# PWM_I2C.net
KiCad netlist of a schematic drawn in Altium Designer
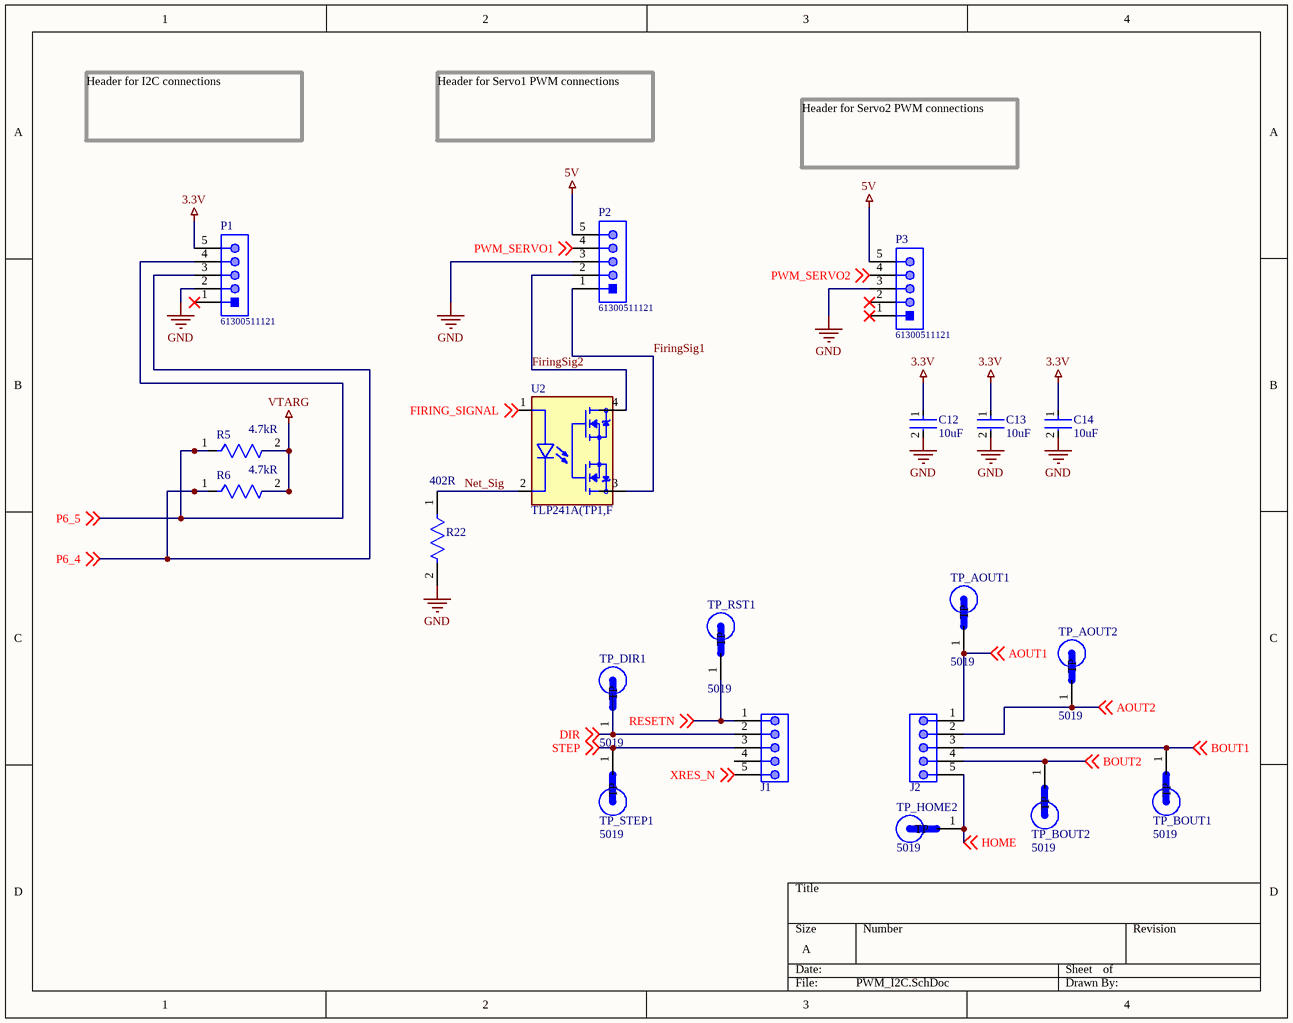
[diagram p0: PWM_I2C.SchDoc]

(export (version "E")
  (design (tool "Eeschema 10.0.6"))
  (components
    (comp (ref "C12")
      (value "10uF")
      (footprint "FP-C0805C-DG-MFG")
      (description "CAP CER 10UF 10V X5R 0805")
      (fields (field (name "TOLERANCE") "10%") (field (name "MANUFACTURER PART NUMBER") "C0805C106K8PACTU"))
      (libsource (lib "Altium Content Vault") (part "11868f565c42a9108669ba33697ecf6"))
    )
    (comp (ref "C13")
      (value "10uF")
      (footprint "FP-C0805C-DG-MFG")
      (description "CAP CER 10UF 10V X5R 0805")
      (fields (field (name "TOLERANCE") "10%") (field (name "MANUFACTURER PART NUMBER") "C0805C106K8PACTU"))
      (libsource (lib "Altium Content Vault") (part "11868f565c42a9108669ba33697ecf6"))
    )
    (comp (ref "C14")
      (value "10uF")
      (footprint "FP-C0805C-DG-MFG")
      (description "CAP CER 10UF 10V X5R 0805")
      (fields (field (name "TOLERANCE") "10%") (field (name "MANUFACTURER PART NUMBER") "C0805C106K8PACTU"))
      (libsource (lib "Altium Content Vault") (part "11868f565c42a9108669ba33697ecf6"))
    )
    (comp (ref "J1")
      (value "CONN_HEADER_MALE_1x5")
      (footprint "HDR1X5")
      (description "Header, 5-Pin")
      (libsource (lib "") (part "CONN_HEADER_MALE_1x5_1"))
    )
    (comp (ref "J2")
      (value "CONN_HEADER_MALE_1x5")
      (footprint "HDR1X5")
      (description "Header, 5-Pin")
      (libsource (lib "Connectors") (part "CONN_HEADER_MALE_1x5"))
    )
    (comp (ref "P1")
      (value "61300511121")
      (footprint "61300511121")
      (description "THT Vertical Pin Header WR-PHD, Pitch 2.54 mm, Single Row, 5 pins")
      (fields (field (name "MANUFACTURER") "Wurth Elektronik") (field (name "PUBLISHER") "WurthElektronik"))
      (libsource (lib "Altium Content Vault") (part "WE-CN-1P-M-R5"))
    )
    (comp (ref "P2")
      (value "61300511121")
      (footprint "61300511121")
      (description "THT Vertical Pin Header WR-PHD, Pitch 2.54 mm, Single Row, 5 pins")
      (fields (field (name "MANUFACTURER") "Wurth Elektronik") (field (name "PUBLISHER") "WurthElektronik"))
      (libsource (lib "Altium Content Vault") (part "WE-CN-1P-M-R5"))
    )
    (comp (ref "P3")
      (value "61300511121")
      (footprint "61300511121")
      (description "THT Vertical Pin Header WR-PHD, Pitch 2.54 mm, Single Row, 5 pins")
      (fields (field (name "MANUFACTURER") "Wurth Elektronik") (field (name "PUBLISHER") "WurthElektronik"))
      (libsource (lib "Altium Content Vault") (part "WE-CN-1P-M-R5"))
    )
    (comp (ref "R5")
      (value "RMCF0805JT4K70")
      (footprint "FP-RMCF0805-MFG")
      (description "4.7kΩ ±5% 0.125W 0805 Thick Film Chip Resistor AEC-Q200 compliant")
      (fields
        (field (name "RESISTANCE") "4.7kR")
        (field (name "TOLERANCE") "5%")
        (field (name "MANUFACTURER") "Stackpole Electronics")
      )
      (libsource (lib "Altium Content Vault") (part "1029c3af85768c4190bb7ad29bc67b5"))
    )
    (comp (ref "R6")
      (value "RMCF0805JT4K70")
      (footprint "FP-RMCF0805-MFG")
      (description "4.7kΩ ±5% 0.125W 0805 Thick Film Chip Resistor AEC-Q200 compliant")
      (fields
        (field (name "RESISTANCE") "4.7kR")
        (field (name "TOLERANCE") "5%")
        (field (name "MANUFACTURER") "Stackpole Electronics")
      )
      (libsource (lib "Altium Content Vault") (part "1029c3af85768c4190bb7ad29bc67b5"))
    )
    (comp (ref "R22")
      (value "RMCF0805FT402R")
      (footprint "FP-RMCF0805-IPC_C")
      (description "402Ω ±1% 0.125W 0805 Thick Film Chip Resistor AEC-Q200 compliant")
      (fields
        (field (name "RESISTANCE") "402R")
        (field (name "TOLERANCE") "1%")
        (field (name "MANUFACTURER") "Stackpole Electronics")
      )
      (libsource (lib "Altium Content Vault") (part "1029c3af85768c4190bb7ad29bc67b5"))
    )
    (comp (ref "TP_AOUT1")
      (value "5019")
      (footprint "TP380X203")
      (description "PC Test Point, Miniature Phosphor Bronze, Silver Plating Surface Mount Mounting Type")
      (fields (field (name "MF") "Keystone Electronics") (field (name "DIGI-KEY_PART_NUMBER") "36-5019CT-ND"))
      (libsource (lib "5019TP") (part "5019"))
    )
    (comp (ref "TP_AOUT2")
      (value "5019")
      (footprint "TP380X203")
      (description "PC Test Point, Miniature Phosphor Bronze, Silver Plating Surface Mount Mounting Type")
      (fields (field (name "MF") "Keystone Electronics") (field (name "DIGI-KEY_PART_NUMBER") "36-5019CT-ND"))
      (libsource (lib "5019TP") (part "5019"))
    )
    (comp (ref "TP_BOUT1")
      (value "5019")
      (footprint "TP380X203")
      (description "PC Test Point, Miniature Phosphor Bronze, Silver Plating Surface Mount Mounting Type")
      (fields (field (name "MF") "Keystone Electronics") (field (name "DIGI-KEY_PART_NUMBER") "36-5019CT-ND"))
      (libsource (lib "5019TP") (part "5019"))
    )
    (comp (ref "TP_BOUT2")
      (value "5019")
      (footprint "TP380X203")
      (description "PC Test Point, Miniature Phosphor Bronze, Silver Plating Surface Mount Mounting Type")
      (fields (field (name "MF") "Keystone Electronics") (field (name "DIGI-KEY_PART_NUMBER") "36-5019CT-ND"))
      (libsource (lib "5019TP") (part "5019"))
    )
    (comp (ref "TP_DIR1")
      (value "5019")
      (footprint "TP380X203")
      (description "PC Test Point, Miniature Phosphor Bronze, Silver Plating Surface Mount Mounting Type")
      (fields (field (name "MF") "Keystone Electronics") (field (name "DIGI-KEY_PART_NUMBER") "36-5019CT-ND"))
      (libsource (lib "5019TP") (part "5019"))
    )
    (comp (ref "TP_HOME2")
      (value "5019")
      (footprint "TP380X203")
      (description "PC Test Point, Miniature Phosphor Bronze, Silver Plating Surface Mount Mounting Type")
      (fields (field (name "MF") "Keystone Electronics") (field (name "DIGI-KEY_PART_NUMBER") "36-5019CT-ND"))
      (libsource (lib "5019TP") (part "5019"))
    )
    (comp (ref "TP_RST1")
      (value "5019")
      (footprint "TP380X203")
      (description "PC Test Point, Miniature Phosphor Bronze, Silver Plating Surface Mount Mounting Type")
      (fields (field (name "MF") "Keystone Electronics") (field (name "DIGI-KEY_PART_NUMBER") "36-5019CT-ND"))
      (libsource (lib "5019TP") (part "5019"))
    )
    (comp (ref "TP_STEP1")
      (value "5019")
      (footprint "TP380X203")
      (description "PC Test Point, Miniature Phosphor Bronze, Silver Plating Surface Mount Mounting Type")
      (fields (field (name "MF") "Keystone Electronics") (field (name "DIGI-KEY_PART_NUMBER") "36-5019CT-ND"))
      (libsource (lib "5019TP") (part "5019"))
    )
    (comp (ref "U2")
      (value "TLP241A(TP1,F")
      (footprint "SOIC254P1000X425-4N:SOIC254P1000X425-4N")
      (description "Relay Ssr 25MA 1.4V Dc-in 2A 40V Dc-out 4-PIN DIP T/r")
      (fields (field (name "MF") "Toshiba Semiconductor") (field (name "MANUFACTURER") "Toshiba"))
      (libsource (lib "TLP241A(TP1,F") (part "TLP241A(TP1,F"))
    )
  )
  (nets
    (net (code "1") (name "/FiringSig1") (class "Default")
      (node (ref "P2") (pin "1") (pinfunction "1_1") (pintype "passive"))
      (node (ref "U2") (pin "3") (pinfunction "D1_3") (pintype "passive"))
    )
    (net (code "2") (name "/FiringSig2") (class "Default")
      (node (ref "P2") (pin "2") (pinfunction "2_2") (pintype "passive"))
      (node (ref "U2") (pin "4") (pinfunction "D2_4") (pintype "passive"))
    )
    (net (code "3") (name "/Net_Sig") (class "Default")
      (node (ref "R22") (pin "1") (pinfunction "1_1") (pintype "passive"))
      (node (ref "U2") (pin "2") (pinfunction "C_2") (pintype "passive"))
    )
    (net (code "4") (name "3.3V") (class "Default")
      (node (ref "C12") (pin "1") (pinfunction "1_1") (pintype "passive"))
      (node (ref "C13") (pin "1") (pinfunction "1_1") (pintype "passive"))
      (node (ref "C14") (pin "1") (pinfunction "1_1") (pintype "passive"))
      (node (ref "P1") (pin "5") (pinfunction "5_5") (pintype "passive"))
    )
    (net (code "5") (name "5V") (class "Default")
      (node (ref "P2") (pin "5") (pinfunction "5_5") (pintype "passive"))
      (node (ref "P3") (pin "5") (pinfunction "5_5") (pintype "passive"))
    )
    (net (code "6") (name "AOUT1") (class "Default")
      (node (ref "J2") (pin "1") (pinfunction "1_1") (pintype "passive"))
      (node (ref "TP_AOUT1") (pin "1") (pinfunction "TP_1") (pintype "passive"))
    )
    (net (code "7") (name "AOUT2") (class "Default")
      (node (ref "J2") (pin "2") (pinfunction "2_2") (pintype "passive"))
      (node (ref "TP_AOUT2") (pin "1") (pinfunction "TP_1") (pintype "passive"))
    )
    (net (code "8") (name "BOUT1") (class "Default")
      (node (ref "J2") (pin "3") (pinfunction "3_3") (pintype "passive"))
      (node (ref "TP_BOUT1") (pin "1") (pinfunction "TP_1") (pintype "passive"))
    )
    (net (code "9") (name "BOUT2") (class "Default")
      (node (ref "J2") (pin "4") (pinfunction "4_4") (pintype "passive"))
      (node (ref "TP_BOUT2") (pin "1") (pinfunction "TP_1") (pintype "passive"))
    )
    (net (code "10") (name "DIR") (class "Default")
      (node (ref "J1") (pin "2") (pinfunction "2_2") (pintype "passive"))
      (node (ref "TP_DIR1") (pin "1") (pinfunction "TP_1") (pintype "passive"))
    )
    (net (code "11") (name "FIRING_SIGNAL") (class "Default")
      (node (ref "U2") (pin "1") (pinfunction "A_1") (pintype "passive"))
    )
    (net (code "12") (name "GND") (class "Default")
      (node (ref "C12") (pin "2") (pinfunction "2_2") (pintype "passive"))
      (node (ref "C13") (pin "2") (pinfunction "2_2") (pintype "passive"))
      (node (ref "C14") (pin "2") (pinfunction "2_2") (pintype "passive"))
      (node (ref "P1") (pin "2") (pinfunction "2_2") (pintype "passive"))
      (node (ref "P2") (pin "3") (pinfunction "3_3") (pintype "passive"))
      (node (ref "P3") (pin "3") (pinfunction "3_3") (pintype "passive"))
      (node (ref "R22") (pin "2") (pinfunction "2_2") (pintype "passive"))
    )
    (net (code "13") (name "HOME") (class "Default")
      (node (ref "J2") (pin "5") (pinfunction "5_5") (pintype "passive"))
      (node (ref "TP_HOME2") (pin "1") (pinfunction "TP_1") (pintype "passive"))
    )
    (net (code "14") (name "P6_4") (class "Default")
      (node (ref "P1") (pin "3") (pinfunction "3_3") (pintype "passive"))
      (node (ref "R6") (pin "1") (pinfunction "1_1") (pintype "passive"))
    )
    (net (code "15") (name "P6_5") (class "Default")
      (node (ref "P1") (pin "4") (pinfunction "4_4") (pintype "passive"))
      (node (ref "R5") (pin "1") (pinfunction "1_1") (pintype "passive"))
    )
    (net (code "16") (name "PWM_SERVO1") (class "Default")
      (node (ref "P2") (pin "4") (pinfunction "4_4") (pintype "passive"))
    )
    (net (code "17") (name "PWM_SERVO2") (class "Default")
      (node (ref "P3") (pin "4") (pinfunction "4_4") (pintype "passive"))
    )
    (net (code "18") (name "RESETN") (class "Default")
      (node (ref "J1") (pin "1") (pinfunction "1_1") (pintype "passive"))
      (node (ref "TP_RST1") (pin "1") (pinfunction "TP_1") (pintype "passive"))
    )
    (net (code "19") (name "STEP") (class "Default")
      (node (ref "J1") (pin "3") (pinfunction "3_3") (pintype "passive"))
      (node (ref "TP_STEP1") (pin "1") (pinfunction "TP_1") (pintype "passive"))
    )
    (net (code "20") (name "VTARG") (class "Default")
      (node (ref "R5") (pin "2") (pinfunction "2_2") (pintype "passive"))
      (node (ref "R6") (pin "2") (pinfunction "2_2") (pintype "passive"))
    )
    (net (code "21") (name "XRES_N") (class "Default")
      (node (ref "J1") (pin "5") (pinfunction "5_5") (pintype "passive"))
    )
    (net (code "22") (name "unconnected-(J1-Pad4)") (class "Default")
      (node (ref "J1") (pin "4") (pinfunction "4_4") (pintype "passive"))
    )
    (net (code "23") (name "unconnected-(P1-Pad1)") (class "Default")
      (node (ref "P1") (pin "1") (pinfunction "1_1") (pintype "passive+no_connect"))
    )
    (net (code "24") (name "unconnected-(P3-Pad1)") (class "Default")
      (node (ref "P3") (pin "1") (pinfunction "1_1") (pintype "passive+no_connect"))
    )
    (net (code "25") (name "unconnected-(P3-Pad2)") (class "Default")
      (node (ref "P3") (pin "2") (pinfunction "2_2") (pintype "passive+no_connect"))
    )
  )
)
